# IMX291.net
KiCad netlist of a schematic drawn in Altium Designer
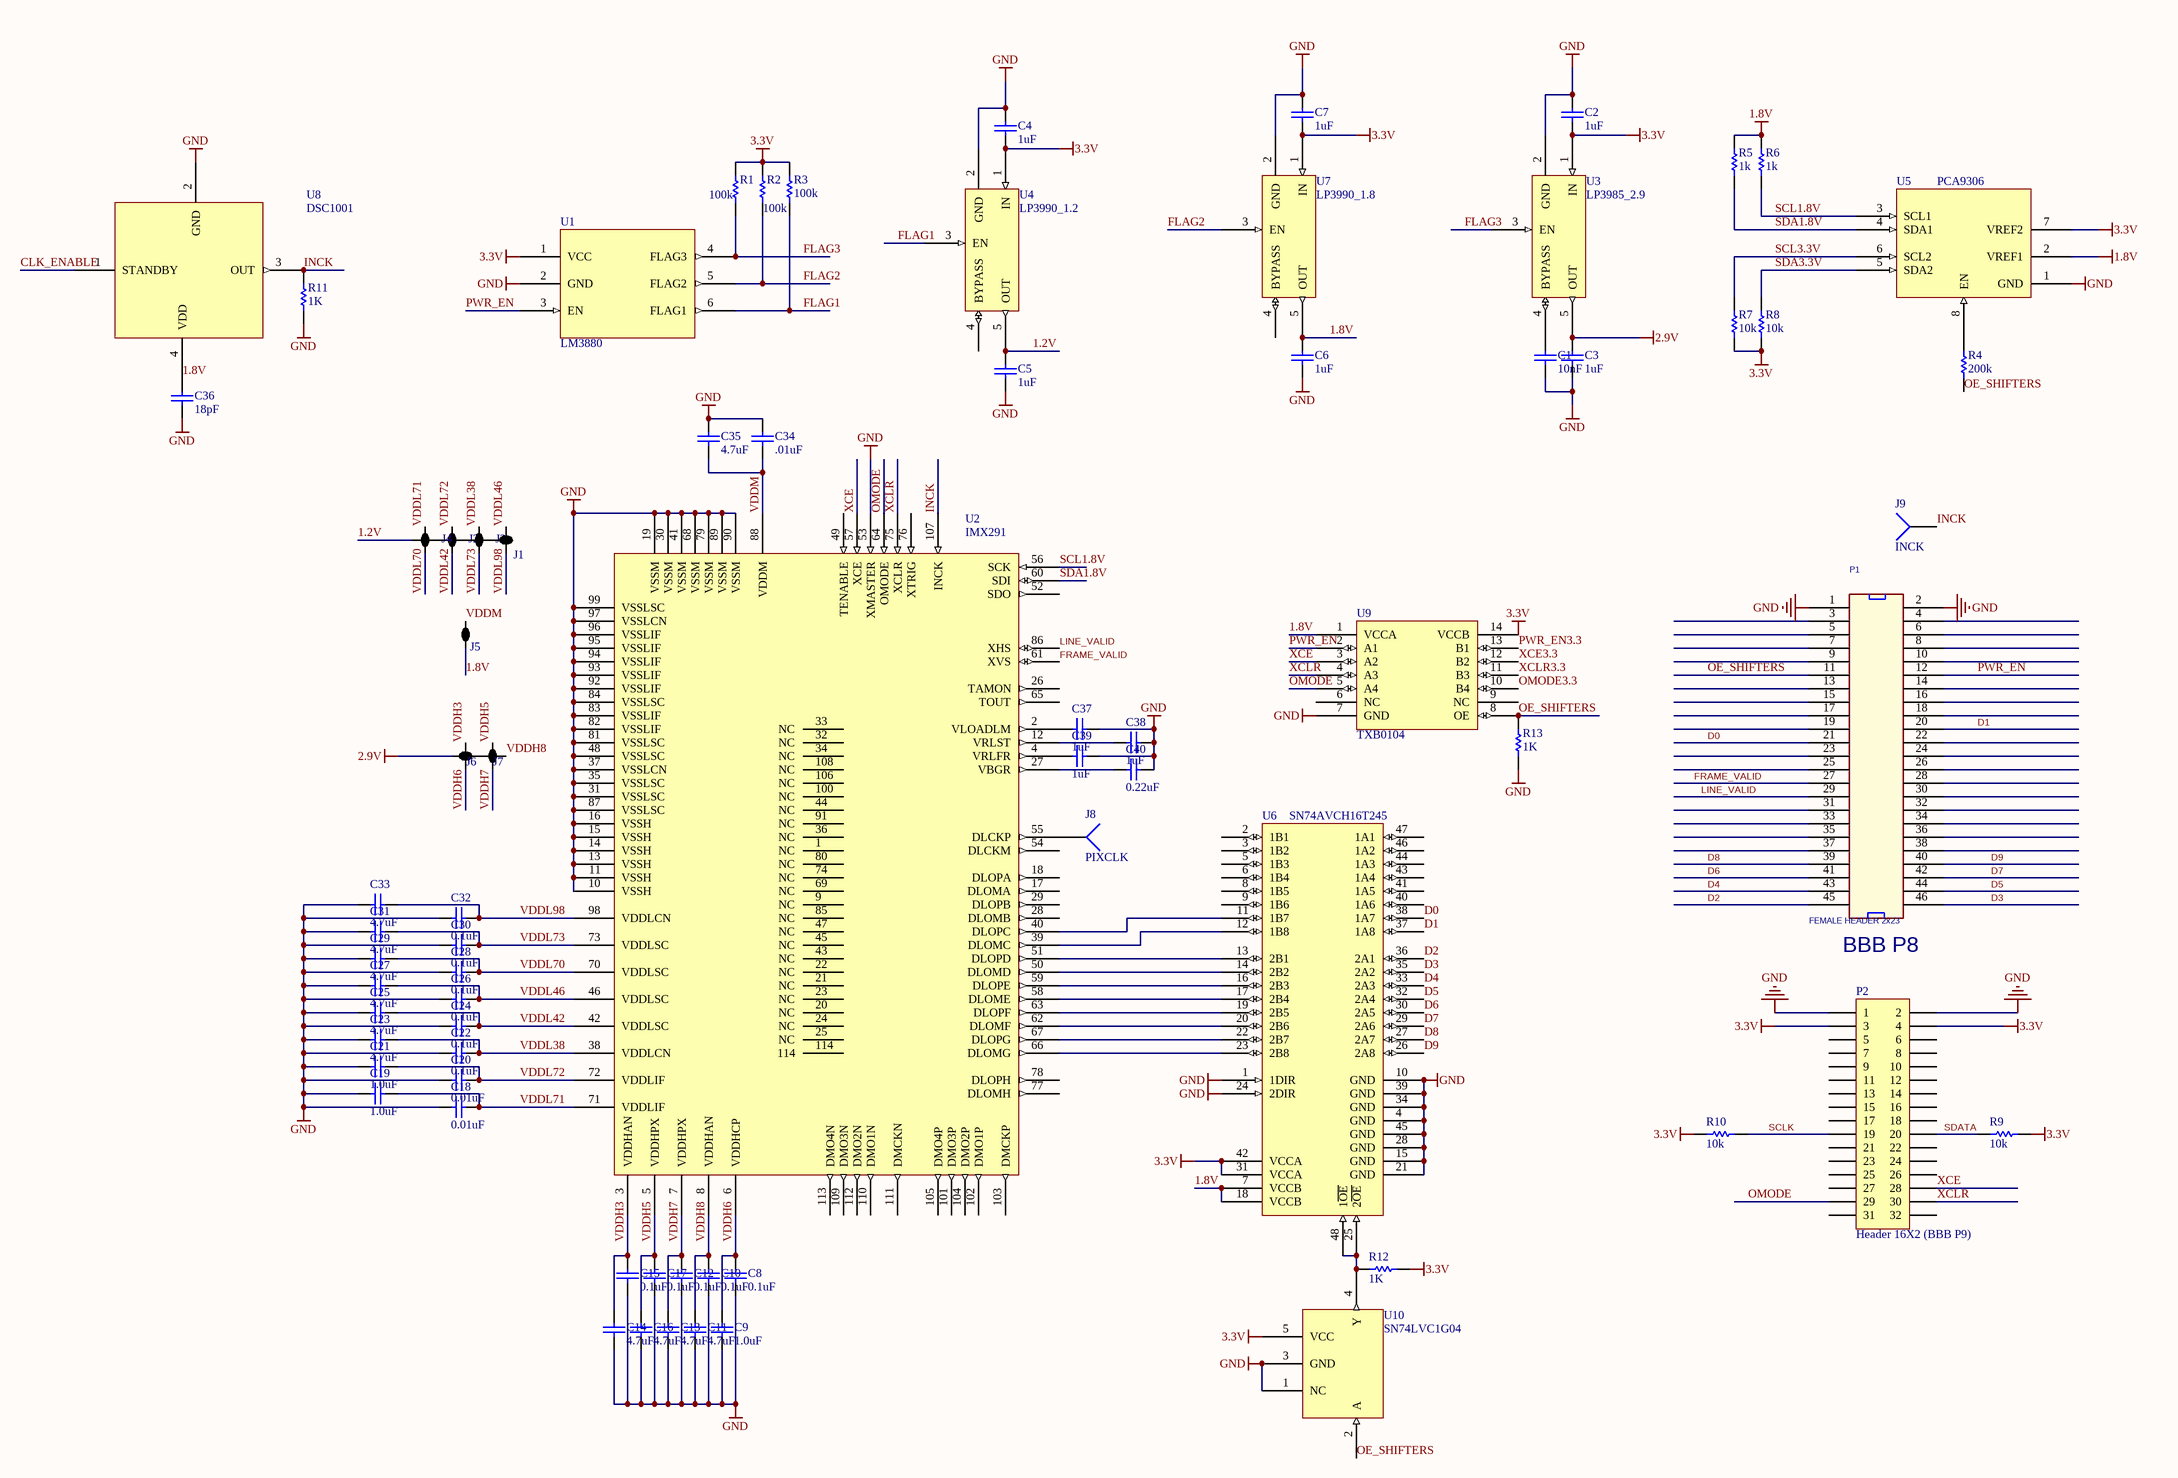
[diagram p0: IMX291.SchDoc]

(export (version "E")
  (design (tool "Eeschema 10.0.6"))
  (components
    (comp (ref "C1") (value "10nF") (footprint "0603") (libsource (lib "IMX291") (part "cap")))
    (comp (ref "C2") (value "1uF") (footprint "0603") (libsource (lib "IMX291") (part "cap")))
    (comp (ref "C3") (value "1uF") (footprint "0603") (libsource (lib "IMX291") (part "cap")))
    (comp (ref "C4") (value "1uF") (footprint "0603") (libsource (lib "IMX291") (part "cap")))
    (comp (ref "C5") (value "1uF") (footprint "0603") (libsource (lib "IMX291") (part "cap")))
    (comp (ref "C6") (value "1uF") (footprint "0603") (libsource (lib "IMX291") (part "cap")))
    (comp (ref "C7") (value "1uF") (footprint "0603") (libsource (lib "IMX291") (part "cap")))
    (comp (ref "C8") (value "0.1uF") (footprint "0603") (libsource (lib "IMX291") (part "cap")))
    (comp (ref "C9") (value "1.0uF") (footprint "0603") (libsource (lib "IMX291") (part "cap")))
    (comp (ref "C10") (value "0.1uF") (footprint "0603") (libsource (lib "IMX291") (part "cap")))
    (comp (ref "C11") (value "4.7uF") (footprint "0603") (libsource (lib "IMX291") (part "cap")))
    (comp (ref "C12") (value "0.1uF") (footprint "0603") (libsource (lib "IMX291") (part "cap")))
    (comp (ref "C13") (value "4.7uF") (footprint "0603") (libsource (lib "IMX291") (part "cap")))
    (comp (ref "C14") (value "4.7uF") (footprint "0603") (libsource (lib "IMX291") (part "cap")))
    (comp (ref "C15") (value "0.1uF") (footprint "0603") (libsource (lib "IMX291") (part "cap")))
    (comp (ref "C16") (value "4.7uF") (footprint "0603") (libsource (lib "IMX291") (part "cap")))
    (comp (ref "C17") (value "0.1uF") (footprint "0603") (libsource (lib "IMX291") (part "cap")))
    (comp (ref "C18") (value "0.01uF") (footprint "0603") (libsource (lib "IMX291") (part "cap")))
    (comp (ref "C19") (value "1.0uF") (footprint "0603") (libsource (lib "IMX291") (part "cap")))
    (comp (ref "C20") (value "0.01uF") (footprint "0603") (libsource (lib "IMX291") (part "cap")))
    (comp (ref "C21") (value "1.0uF") (footprint "0603") (libsource (lib "IMX291") (part "cap")))
    (comp (ref "C22") (value "0.1uF") (footprint "0603") (libsource (lib "IMX291") (part "cap")))
    (comp (ref "C23") (value "4.7uF") (footprint "0603") (libsource (lib "IMX291") (part "cap")))
    (comp (ref "C24") (value "0.1uF") (footprint "0603") (libsource (lib "IMX291") (part "cap")))
    (comp (ref "C25") (value "4.7uF") (footprint "0603") (libsource (lib "IMX291") (part "cap")))
    (comp (ref "C26") (value "0.1uF") (footprint "0603") (libsource (lib "IMX291") (part "cap")))
    (comp (ref "C27") (value "4.7uF") (footprint "0603") (libsource (lib "IMX291") (part "cap")))
    (comp (ref "C28") (value "0.1uF") (footprint "0603") (libsource (lib "IMX291") (part "cap")))
    (comp (ref "C29") (value "4.7uF") (footprint "0603") (libsource (lib "IMX291") (part "cap")))
    (comp (ref "C30") (value "0.1uF") (footprint "0603") (libsource (lib "IMX291") (part "cap")))
    (comp (ref "C31") (value "4.7uF") (footprint "0603") (libsource (lib "IMX291") (part "cap")))
    (comp (ref "C32") (value "0.1uF") (footprint "0603") (libsource (lib "IMX291") (part "cap")))
    (comp (ref "C33") (value "4.7uF") (footprint "0603") (libsource (lib "IMX291") (part "cap")))
    (comp (ref "C34") (value ".01uF") (footprint "0603") (libsource (lib "IMX291") (part "cap")))
    (comp (ref "C35") (value "4.7uF") (footprint "0603") (libsource (lib "IMX291") (part "cap")))
    (comp (ref "C36") (value "18pF") (footprint "0603") (libsource (lib "IMX291") (part "cap")))
    (comp (ref "C37") (value "1uF") (footprint "0603") (libsource (lib "IMX291") (part "cap")))
    (comp (ref "C38") (value "1uF") (footprint "0603") (libsource (lib "IMX291") (part "cap")))
    (comp (ref "C39") (value "1uF") (footprint "0603") (libsource (lib "IMX291") (part "cap")))
    (comp (ref "C40") (value "0.22uF") (footprint "0603") (libsource (lib "IMX291") (part "cap")))
    (comp (ref "J1")
      (value "3 way net tie junction T shape")
      (footprint "3wayT_LP")
      (libsource (lib "NetTieLib") (part "3wayT"))
    )
    (comp (ref "J2")
      (value "4 way net tie junction")
      (footprint "4way_LP")
      (libsource (lib "") (part "4way_1"))
    )
    (comp (ref "J3")
      (value "4 way net tie junction")
      (footprint "4way_LP")
      (libsource (lib "") (part "4way_1"))
    )
    (comp (ref "J4")
      (value "4 way net tie junction")
      (footprint "4way_LP")
      (libsource (lib "") (part "4way_1"))
    )
    (comp (ref "J5")
      (value "2 way net tie junction")
      (footprint "2way_LP")
      (libsource (lib "NetTieLib") (part "2way"))
    )
    (comp (ref "J6")
      (value "4 way net tie junction")
      (footprint "4way_LP")
      (libsource (lib "NetTieLib") (part "4way"))
    )
    (comp (ref "J7")
      (value "4 way net tie junction")
      (footprint "4way_LP")
      (libsource (lib "") (part "4way_1"))
    )
    (comp (ref "J8")
      (value "PIXCLK")
      (footprint "PIN1")
      (description "Socket")
      (fields (field (name "PUBLISHER") "Altium Limited"))
      (libsource (lib "Miscellaneous Connectors") (part "Socket"))
    )
    (comp (ref "J9")
      (value "INCK")
      (footprint "PIN1")
      (description "Socket")
      (fields (field (name "PUBLISHER") "Altium Limited"))
      (libsource (lib "Miscellaneous Connectors") (part "Socket"))
    )
    (comp (ref "P1")
      (value "FEMALE HEADER 2x23")
      (description "CONN HEADER FMAL 46PS.1\" DL GOLD")
      (fields
        (field (name "MANUFACTURER") "Sullins Connector Solutions")
        (field (name "MANUFACTURER PART NUMBER") "PPPC232LFBN-RC")
      )
      (libsource (lib "IMX291") (part "HDR_46_F_2_0.1_0.1"))
    )
    (comp (ref "P2")
      (value "Header 16X2 (BBB P9)")
      (footprint "HDR2X16")
      (description "Header, 16-Pin, Dual row")
      (fields (field (name "PUBLISHER") "Altium Limited"))
      (libsource (lib "Miscellaneous Connectors") (part "Header 16X2"))
    )
    (comp (ref "R1")
      (value "100k")
      (footprint "0603")
      (description "resistor")
      (libsource (lib "IMX291") (part "res"))
    )
    (comp (ref "R2")
      (value "100k")
      (footprint "0603")
      (description "resistor")
      (libsource (lib "IMX291") (part "res"))
    )
    (comp (ref "R3")
      (value "100k")
      (footprint "0603")
      (description "resistor")
      (libsource (lib "IMX291") (part "res"))
    )
    (comp (ref "R4")
      (value "200k")
      (footprint "0603")
      (description "resistor")
      (libsource (lib "IMX291") (part "res"))
    )
    (comp (ref "R5")
      (value "1k")
      (footprint "0603")
      (description "resistor")
      (libsource (lib "IMX291") (part "res"))
    )
    (comp (ref "R6")
      (value "1k")
      (footprint "0603")
      (description "resistor")
      (libsource (lib "IMX291") (part "res"))
    )
    (comp (ref "R7")
      (value "10k")
      (footprint "0603")
      (description "resistor")
      (libsource (lib "IMX291") (part "res"))
    )
    (comp (ref "R8")
      (value "10k")
      (footprint "0603")
      (description "resistor")
      (libsource (lib "IMX291") (part "res"))
    )
    (comp (ref "R9")
      (value "10k")
      (footprint "0603")
      (description "resistor")
      (libsource (lib "IMX291") (part "res"))
    )
    (comp (ref "R10")
      (value "10k")
      (footprint "0603")
      (description "resistor")
      (libsource (lib "IMX291") (part "res"))
    )
    (comp (ref "R11") (value "1K") (footprint "0603") (libsource (lib "") (part "res_1")))
    (comp (ref "R12") (value "1K") (footprint "0603") (libsource (lib "") (part "res_1")))
    (comp (ref "R13") (value "1K") (footprint "0603") (libsource (lib "") (part "res_1")))
    (comp (ref "U1") (value "LM3880") (footprint "SOT23-6_M") (libsource (lib "IMX291") (part "LM3880")))
    (comp (ref "U2")
      (value "IMX291")
      (footprint "LGA110C80P14X11_1200X930X350")
      (libsource (lib "IMX291") (part "IMX291"))
    )
    (comp (ref "U3") (value "LP3985_2.9") (footprint "DBV005") (libsource (lib "IMX291") (part "LP3985")))
    (comp (ref "U4") (value "LP3990_1.2") (footprint "DBV005") (libsource (lib "IMX291") (part "LP3990")))
    (comp (ref "U5") (value "PCA9306") (footprint "D008_M") (libsource (lib "IMX291") (part "PCA9306")))
    (comp (ref "U6")
      (value "SN74AVCH16T245")
      (footprint "TSSOP48")
      (libsource (lib "IMX291") (part "SN74AVCH16T245"))
    )
    (comp (ref "U7") (value "LP3990_1.8") (footprint "DBV005") (libsource (lib "IMX291") (part "LP3990")))
    (comp (ref "U8") (value "DSC1001") (footprint "DSC1001") (libsource (lib "IMX291") (part "DSC1001")))
    (comp (ref "U9") (value "TXB0104") (footprint "TSSOP14_M") (libsource (lib "IMX291") (part "TXB0104")))
    (comp (ref "U10")
      (value "SN74LVC1G04")
      (footprint "DBV005")
      (libsource (lib "IMX291") (part "SN74LVC1G04"))
    )
  )
  (nets
    (net (code "1") (name "/1.2V") (class "Default")
      (node (ref "C5") (pin "2") (pinfunction "2_2") (pintype "passive"))
      (node (ref "J4") (pin "3") (pinfunction "3_3") (pintype "passive"))
      (node (ref "U4") (pin "5") (pinfunction "OUT_5") (pintype "output"))
    )
    (net (code "2") (name "/CLK_ENABLE") (class "Default")
      (node (ref "U8") (pin "1") (pinfunction "STANDBY_1") (pintype "passive"))
    )
    (net (code "3") (name "/D0") (class "Default")
      (node (ref "P1") (pin "21") (pinfunction "11_21") (pintype "passive"))
      (node (ref "U6") (pin "38") (pinfunction "1A7_38") (pintype "bidirectional"))
    )
    (net (code "4") (name "/D1") (class "Default")
      (node (ref "P1") (pin "20") (pinfunction "35_20") (pintype "passive"))
      (node (ref "U6") (pin "37") (pinfunction "1A8_37") (pintype "bidirectional"))
    )
    (net (code "5") (name "/D2") (class "Default")
      (node (ref "P1") (pin "45") (pinfunction "23_45") (pintype "passive"))
      (node (ref "U6") (pin "36") (pinfunction "2A1_36") (pintype "bidirectional"))
    )
    (net (code "6") (name "/D3") (class "Default")
      (node (ref "P1") (pin "46") (pinfunction "48_46") (pintype "passive"))
      (node (ref "U6") (pin "35") (pinfunction "2A2_35") (pintype "bidirectional"))
    )
    (net (code "7") (name "/D4") (class "Default")
      (node (ref "P1") (pin "43") (pinfunction "22_43") (pintype "passive"))
      (node (ref "U6") (pin "33") (pinfunction "2A3_33") (pintype "bidirectional"))
    )
    (net (code "8") (name "/D5") (class "Default")
      (node (ref "P1") (pin "44") (pinfunction "47_44") (pintype "passive"))
      (node (ref "U6") (pin "32") (pinfunction "2A4_32") (pintype "bidirectional"))
    )
    (net (code "9") (name "/D6") (class "Default")
      (node (ref "P1") (pin "41") (pinfunction "21_41") (pintype "passive"))
      (node (ref "U6") (pin "30") (pinfunction "2A5_30") (pintype "bidirectional"))
    )
    (net (code "10") (name "/D7") (class "Default")
      (node (ref "P1") (pin "42") (pinfunction "46_42") (pintype "passive"))
      (node (ref "U6") (pin "29") (pinfunction "2A6_29") (pintype "bidirectional"))
    )
    (net (code "11") (name "/D8") (class "Default")
      (node (ref "P1") (pin "39") (pinfunction "20_39") (pintype "passive"))
      (node (ref "U6") (pin "27") (pinfunction "2A7_27") (pintype "bidirectional"))
    )
    (net (code "12") (name "/D9") (class "Default")
      (node (ref "P1") (pin "40") (pinfunction "45_40") (pintype "passive"))
      (node (ref "U6") (pin "26") (pinfunction "2A8_26") (pintype "bidirectional"))
    )
    (net (code "13") (name "/FLAG1") (class "Default")
      (node (ref "R3") (pin "1") (pinfunction "1_1") (pintype "passive"))
      (node (ref "U1") (pin "6") (pinfunction "FLAG1_6") (pintype "output"))
      (node (ref "U4") (pin "3") (pinfunction "EN_3") (pintype "input"))
    )
    (net (code "14") (name "/FLAG2") (class "Default")
      (node (ref "R2") (pin "1") (pinfunction "1_1") (pintype "passive"))
      (node (ref "U1") (pin "5") (pinfunction "FLAG2_5") (pintype "output"))
      (node (ref "U7") (pin "3") (pinfunction "EN_3") (pintype "input"))
    )
    (net (code "15") (name "/FLAG3") (class "Default")
      (node (ref "R1") (pin "1") (pinfunction "1_1") (pintype "passive"))
      (node (ref "U1") (pin "4") (pinfunction "FLAG3_4") (pintype "output"))
      (node (ref "U3") (pin "3") (pinfunction "EN_3") (pintype "input"))
    )
    (net (code "16") (name "/FRAME_VALID") (class "Default")
      (node (ref "P1") (pin "27") (pinfunction "14_27") (pintype "passive"))
      (node (ref "U2") (pin "61") (pinfunction "XVS_61") (pintype "bidirectional"))
    )
    (net (code "17") (name "/INCK") (class "Default")
      (node (ref "J9") (pin "1") (pinfunction "1_1") (pintype "passive"))
      (node (ref "R11") (pin "2") (pinfunction "2_2") (pintype "passive"))
      (node (ref "U2") (pin "107") (pinfunction "INCK_107") (pintype "input"))
      (node (ref "U8") (pin "3") (pinfunction "OUT_3") (pintype "output"))
    )
    (net (code "18") (name "/LINE_VALID") (class "Default")
      (node (ref "P1") (pin "29") (pinfunction "15_29") (pintype "passive"))
      (node (ref "U2") (pin "86") (pinfunction "XHS_86") (pintype "bidirectional"))
    )
    (net (code "19") (name "/OE_SHIFTERS") (class "Default")
      (node (ref "P1") (pin "11") (pinfunction "6_11") (pintype "passive"))
      (node (ref "R13") (pin "2") (pinfunction "2_2") (pintype "passive"))
      (node (ref "R4") (pin "1") (pinfunction "1_1") (pintype "passive"))
      (node (ref "U10") (pin "2") (pinfunction "A_2") (pintype "input"))
      (node (ref "U9") (pin "8") (pinfunction "OE_8") (pintype "bidirectional"))
    )
    (net (code "20") (name "/OMODE") (class "Default")
      (node (ref "P2") (pin "29") (pinfunction "29_29") (pintype "passive"))
      (node (ref "U2") (pin "64") (pinfunction "OMODE_64") (pintype "input"))
      (node (ref "U9") (pin "5") (pinfunction "A4_5") (pintype "bidirectional"))
    )
    (net (code "21") (name "/OMODE3.3") (class "Default")
      (node (ref "U9") (pin "10") (pinfunction "B4_10") (pintype "bidirectional"))
    )
    (net (code "22") (name "/PWR_EN") (class "Default")
      (node (ref "P1") (pin "12") (pinfunction "31_12") (pintype "passive"))
      (node (ref "U1") (pin "3") (pinfunction "EN_3") (pintype "input"))
      (node (ref "U9") (pin "2") (pinfunction "A1_2") (pintype "bidirectional"))
    )
    (net (code "23") (name "/PWR_EN3.3") (class "Default")
      (node (ref "U9") (pin "13") (pinfunction "B1_13") (pintype "bidirectional"))
    )
    (net (code "24") (name "/SCL1.8V") (class "Default")
      (node (ref "R6") (pin "1") (pinfunction "1_1") (pintype "passive"))
      (node (ref "U2") (pin "56") (pinfunction "SCK_56") (pintype "input"))
      (node (ref "U5") (pin "3") (pinfunction "SCL1_3") (pintype "input"))
    )
    (net (code "25") (name "/SCL3.3V") (class "Default")
      (node (ref "R7") (pin "2") (pinfunction "2_2") (pintype "passive"))
      (node (ref "U5") (pin "6") (pinfunction "SCL2_6") (pintype "input"))
    )
    (net (code "26") (name "/SCLK") (class "Default")
      (node (ref "P2") (pin "19") (pinfunction "19_19") (pintype "passive"))
      (node (ref "R10") (pin "2") (pinfunction "2_2") (pintype "passive"))
    )
    (net (code "27") (name "/SDA1.8V") (class "Default")
      (node (ref "R5") (pin "1") (pinfunction "1_1") (pintype "passive"))
      (node (ref "U2") (pin "60") (pinfunction "SDI_60") (pintype "bidirectional"))
      (node (ref "U5") (pin "4") (pinfunction "SDA1_4") (pintype "input"))
    )
    (net (code "28") (name "/SDA3.3V") (class "Default")
      (node (ref "R8") (pin "2") (pinfunction "2_2") (pintype "passive"))
      (node (ref "U5") (pin "5") (pinfunction "SDA2_5") (pintype "input"))
    )
    (net (code "29") (name "/SDATA") (class "Default")
      (node (ref "P2") (pin "20") (pinfunction "20_20") (pintype "passive"))
      (node (ref "R9") (pin "1") (pinfunction "1_1") (pintype "passive"))
    )
    (net (code "30") (name "/VDDH3") (class "Default")
      (node (ref "C14") (pin "2") (pinfunction "2_2") (pintype "passive"))
      (node (ref "C15") (pin "2") (pinfunction "2_2") (pintype "passive"))
      (node (ref "J6") (pin "2") (pinfunction "2_2") (pintype "passive"))
      (node (ref "U2") (pin "3") (pinfunction "VDDHAN_3") (pintype "power_in"))
    )
    (net (code "31") (name "/VDDH5") (class "Default")
      (node (ref "C16") (pin "2") (pinfunction "2_2") (pintype "passive"))
      (node (ref "C17") (pin "2") (pinfunction "2_2") (pintype "passive"))
      (node (ref "J7") (pin "1") (pinfunction "1_1") (pintype "passive"))
      (node (ref "U2") (pin "5") (pinfunction "VDDHPX_5") (pintype "power_in"))
    )
    (net (code "32") (name "/VDDH6") (class "Default")
      (node (ref "C8") (pin "1") (pinfunction "1_1") (pintype "passive"))
      (node (ref "C9") (pin "1") (pinfunction "1_1") (pintype "passive"))
      (node (ref "J6") (pin "3") (pinfunction "3_3") (pintype "passive"))
      (node (ref "U2") (pin "6") (pinfunction "VDDHCP_6") (pintype "power_in"))
    )
    (net (code "33") (name "/VDDH7") (class "Default")
      (node (ref "C12") (pin "2") (pinfunction "2_2") (pintype "passive"))
      (node (ref "C13") (pin "2") (pinfunction "2_2") (pintype "passive"))
      (node (ref "J7") (pin "4") (pinfunction "4_4") (pintype "passive"))
      (node (ref "U2") (pin "7") (pinfunction "VDDHPX_7") (pintype "power_in"))
    )
    (net (code "34") (name "/VDDH8") (class "Default")
      (node (ref "C10") (pin "2") (pinfunction "2_2") (pintype "passive"))
      (node (ref "C11") (pin "2") (pinfunction "2_2") (pintype "passive"))
      (node (ref "J7") (pin "2") (pinfunction "2_2") (pintype "passive"))
      (node (ref "U2") (pin "8") (pinfunction "VDDHAN_8") (pintype "power_in"))
    )
    (net (code "35") (name "/VDDL38") (class "Default")
      (node (ref "C22") (pin "2") (pinfunction "2_2") (pintype "passive"))
      (node (ref "C23") (pin "2") (pinfunction "2_2") (pintype "passive"))
      (node (ref "J3") (pin "1") (pinfunction "1_1") (pintype "passive"))
      (node (ref "U2") (pin "38") (pinfunction "VDDLCN_38") (pintype "power_in"))
    )
    (net (code "36") (name "/VDDL42") (class "Default")
      (node (ref "C24") (pin "2") (pinfunction "2_2") (pintype "passive"))
      (node (ref "C25") (pin "2") (pinfunction "2_2") (pintype "passive"))
      (node (ref "J2") (pin "4") (pinfunction "4_4") (pintype "passive"))
      (node (ref "U2") (pin "42") (pinfunction "VDDLSC_42") (pintype "power_in"))
    )
    (net (code "37") (name "/VDDL46") (class "Default")
      (node (ref "C26") (pin "2") (pinfunction "2_2") (pintype "passive"))
      (node (ref "C27") (pin "2") (pinfunction "2_2") (pintype "passive"))
      (node (ref "J1") (pin "2") (pinfunction "2_2") (pintype "passive"))
      (node (ref "U2") (pin "46") (pinfunction "VDDLSC_46") (pintype "power_in"))
    )
    (net (code "38") (name "/VDDL70") (class "Default")
      (node (ref "C28") (pin "2") (pinfunction "2_2") (pintype "passive"))
      (node (ref "C29") (pin "2") (pinfunction "2_2") (pintype "passive"))
      (node (ref "J4") (pin "4") (pinfunction "4_4") (pintype "passive"))
      (node (ref "U2") (pin "70") (pinfunction "VDDLSC_70") (pintype "power_in"))
    )
    (net (code "39") (name "/VDDL71") (class "Default")
      (node (ref "C18") (pin "2") (pinfunction "2_2") (pintype "passive"))
      (node (ref "C19") (pin "2") (pinfunction "2_2") (pintype "passive"))
      (node (ref "J4") (pin "1") (pinfunction "1_1") (pintype "passive"))
      (node (ref "U2") (pin "71") (pinfunction "VDDLIF_71") (pintype "power_in"))
    )
    (net (code "40") (name "/VDDL72") (class "Default")
      (node (ref "C20") (pin "2") (pinfunction "2_2") (pintype "passive"))
      (node (ref "C21") (pin "2") (pinfunction "2_2") (pintype "passive"))
      (node (ref "J2") (pin "1") (pinfunction "1_1") (pintype "passive"))
      (node (ref "U2") (pin "72") (pinfunction "VDDLIF_72") (pintype "power_in"))
    )
    (net (code "41") (name "/VDDL73") (class "Default")
      (node (ref "C30") (pin "2") (pinfunction "2_2") (pintype "passive"))
      (node (ref "C31") (pin "2") (pinfunction "2_2") (pintype "passive"))
      (node (ref "J3") (pin "4") (pinfunction "4_4") (pintype "passive"))
      (node (ref "U2") (pin "73") (pinfunction "VDDLSC_73") (pintype "power_in"))
    )
    (net (code "42") (name "/VDDL98") (class "Default")
      (node (ref "C32") (pin "2") (pinfunction "2_2") (pintype "passive"))
      (node (ref "C33") (pin "2") (pinfunction "2_2") (pintype "passive"))
      (node (ref "J1") (pin "3") (pinfunction "3_3") (pintype "passive"))
      (node (ref "U2") (pin "98") (pinfunction "VDDLCN_98") (pintype "power_in"))
    )
    (net (code "43") (name "/VDDM") (class "Default")
      (node (ref "C34") (pin "1") (pinfunction "1_1") (pintype "passive"))
      (node (ref "C35") (pin "1") (pinfunction "1_1") (pintype "passive"))
      (node (ref "J5") (pin "2") (pinfunction "2_2") (pintype "passive"))
      (node (ref "U2") (pin "88") (pinfunction "VDDM_88") (pintype "power_in"))
    )
    (net (code "44") (name "/XCE") (class "Default")
      (node (ref "P2") (pin "28") (pinfunction "28_28") (pintype "passive"))
      (node (ref "U2") (pin "57") (pinfunction "XCE_57") (pintype "input"))
      (node (ref "U9") (pin "3") (pinfunction "A2_3") (pintype "bidirectional"))
    )
    (net (code "45") (name "/XCE3.3") (class "Default")
      (node (ref "U9") (pin "12") (pinfunction "B2_12") (pintype "bidirectional"))
    )
    (net (code "46") (name "/XCLR") (class "Default")
      (node (ref "P2") (pin "30") (pinfunction "30_30") (pintype "passive"))
      (node (ref "U2") (pin "75") (pinfunction "XCLR_75") (pintype "input"))
      (node (ref "U9") (pin "4") (pinfunction "A3_4") (pintype "bidirectional"))
    )
    (net (code "47") (name "/XCLR3.3") (class "Default")
      (node (ref "U9") (pin "11") (pinfunction "B3_11") (pintype "bidirectional"))
    )
    (net (code "48") (name "1.8V") (class "Default")
      (node (ref "C36") (pin "2") (pinfunction "2_2") (pintype "passive"))
      (node (ref "C6") (pin "2") (pinfunction "2_2") (pintype "passive"))
      (node (ref "J5") (pin "1") (pinfunction "1_1") (pintype "passive"))
      (node (ref "R5") (pin "2") (pinfunction "2_2") (pintype "passive"))
      (node (ref "R6") (pin "2") (pinfunction "2_2") (pintype "passive"))
      (node (ref "U5") (pin "2") (pinfunction "VREF1_2") (pintype "power_in"))
      (node (ref "U6") (pin "18") (pinfunction "VCCB_18") (pintype "power_in"))
      (node (ref "U6") (pin "7") (pinfunction "VCCB_7") (pintype "power_in"))
      (node (ref "U7") (pin "5") (pinfunction "OUT_5") (pintype "output"))
      (node (ref "U8") (pin "4") (pinfunction "VDD_4") (pintype "passive"))
      (node (ref "U9") (pin "1") (pinfunction "VCCA_1") (pintype "power_in"))
    )
    (net (code "49") (name "2.9V") (class "Default")
      (node (ref "C3") (pin "2") (pinfunction "2_2") (pintype "passive"))
      (node (ref "J6") (pin "1") (pinfunction "1_1") (pintype "passive"))
      (node (ref "U3") (pin "5") (pinfunction "OUT_5") (pintype "output"))
    )
    (net (code "50") (name "3.3V") (class "Default")
      (node (ref "C2") (pin "1") (pinfunction "1_1") (pintype "passive"))
      (node (ref "C4") (pin "1") (pinfunction "1_1") (pintype "passive"))
      (node (ref "C7") (pin "1") (pinfunction "1_1") (pintype "passive"))
      (node (ref "P2") (pin "3") (pinfunction "3_3") (pintype "passive"))
      (node (ref "P2") (pin "4") (pinfunction "4_4") (pintype "passive"))
      (node (ref "R1") (pin "2") (pinfunction "2_2") (pintype "passive"))
      (node (ref "R10") (pin "1") (pinfunction "1_1") (pintype "passive"))
      (node (ref "R12") (pin "2") (pinfunction "2_2") (pintype "passive"))
      (node (ref "R2") (pin "2") (pinfunction "2_2") (pintype "passive"))
      (node (ref "R3") (pin "2") (pinfunction "2_2") (pintype "passive"))
      (node (ref "R7") (pin "1") (pinfunction "1_1") (pintype "passive"))
      (node (ref "R8") (pin "1") (pinfunction "1_1") (pintype "passive"))
      (node (ref "R9") (pin "2") (pinfunction "2_2") (pintype "passive"))
      (node (ref "U1") (pin "1") (pinfunction "VCC_1") (pintype "power_in"))
      (node (ref "U10") (pin "5") (pinfunction "VCC_5") (pintype "power_in"))
      (node (ref "U3") (pin "1") (pinfunction "IN_1") (pintype "input"))
      (node (ref "U4") (pin "1") (pinfunction "IN_1") (pintype "input"))
      (node (ref "U5") (pin "7") (pinfunction "VREF2_7") (pintype "power_in"))
      (node (ref "U6") (pin "31") (pinfunction "VCCA_31") (pintype "power_in"))
      (node (ref "U6") (pin "42") (pinfunction "VCCA_42") (pintype "power_in"))
      (node (ref "U7") (pin "1") (pinfunction "IN_1") (pintype "input"))
      (node (ref "U9") (pin "14") (pinfunction "VCCB_14") (pintype "power_in"))
    )
    (net (code "51") (name "GND") (class "Default")
      (node (ref "C1") (pin "1") (pinfunction "1_1") (pintype "passive"))
      (node (ref "C10") (pin "1") (pinfunction "1_1") (pintype "passive"))
      (node (ref "C11") (pin "1") (pinfunction "1_1") (pintype "passive"))
      (node (ref "C12") (pin "1") (pinfunction "1_1") (pintype "passive"))
      (node (ref "C13") (pin "1") (pinfunction "1_1") (pintype "passive"))
      (node (ref "C14") (pin "1") (pinfunction "1_1") (pintype "passive"))
      (node (ref "C15") (pin "1") (pinfunction "1_1") (pintype "passive"))
      (node (ref "C16") (pin "1") (pinfunction "1_1") (pintype "passive"))
      (node (ref "C17") (pin "1") (pinfunction "1_1") (pintype "passive"))
      (node (ref "C18") (pin "1") (pinfunction "1_1") (pintype "passive"))
      (node (ref "C19") (pin "1") (pinfunction "1_1") (pintype "passive"))
      (node (ref "C2") (pin "2") (pinfunction "2_2") (pintype "passive"))
      (node (ref "C20") (pin "1") (pinfunction "1_1") (pintype "passive"))
      (node (ref "C21") (pin "1") (pinfunction "1_1") (pintype "passive"))
      (node (ref "C22") (pin "1") (pinfunction "1_1") (pintype "passive"))
      (node (ref "C23") (pin "1") (pinfunction "1_1") (pintype "passive"))
      (node (ref "C24") (pin "1") (pinfunction "1_1") (pintype "passive"))
      (node (ref "C25") (pin "1") (pinfunction "1_1") (pintype "passive"))
      (node (ref "C26") (pin "1") (pinfunction "1_1") (pintype "passive"))
      (node (ref "C27") (pin "1") (pinfunction "1_1") (pintype "passive"))
      (node (ref "C28") (pin "1") (pinfunction "1_1") (pintype "passive"))
      (node (ref "C29") (pin "1") (pinfunction "1_1") (pintype "passive"))
      (node (ref "C3") (pin "1") (pinfunction "1_1") (pintype "passive"))
      (node (ref "C30") (pin "1") (pinfunction "1_1") (pintype "passive"))
      (node (ref "C31") (pin "1") (pinfunction "1_1") (pintype "passive"))
      (node (ref "C32") (pin "1") (pinfunction "1_1") (pintype "passive"))
      (node (ref "C33") (pin "1") (pinfunction "1_1") (pintype "passive"))
      (node (ref "C34") (pin "2") (pinfunction "2_2") (pintype "passive"))
      (node (ref "C35") (pin "2") (pinfunction "2_2") (pintype "passive"))
      (node (ref "C36") (pin "1") (pinfunction "1_1") (pintype "passive"))
      (node (ref "C37") (pin "2") (pinfunction "2_2") (pintype "passive"))
      (node (ref "C38") (pin "2") (pinfunction "2_2") (pintype "passive"))
      (node (ref "C39") (pin "2") (pinfunction "2_2") (pintype "passive"))
      (node (ref "C4") (pin "2") (pinfunction "2_2") (pintype "passive"))
      (node (ref "C40") (pin "2") (pinfunction "2_2") (pintype "passive"))
      (node (ref "C5") (pin "1") (pinfunction "1_1") (pintype "passive"))
      (node (ref "C6") (pin "1") (pinfunction "1_1") (pintype "passive"))
      (node (ref "C7") (pin "2") (pinfunction "2_2") (pintype "passive"))
      (node (ref "C8") (pin "2") (pinfunction "2_2") (pintype "passive"))
      (node (ref "C9") (pin "2") (pinfunction "2_2") (pintype "passive"))
      (node (ref "P1") (pin "1") (pinfunction "1_1") (pintype "passive"))
      (node (ref "P1") (pin "2") (pinfunction "26_2") (pintype "passive"))
      (node (ref "P2") (pin "1") (pinfunction "1_1") (pintype "passive"))
      (node (ref "P2") (pin "2") (pinfunction "2_2") (pintype "passive"))
      (node (ref "R11") (pin "1") (pinfunction "1_1") (pintype "passive"))
      (node (ref "R13") (pin "1") (pinfunction "1_1") (pintype "passive"))
      (node (ref "U1") (pin "2") (pinfunction "GND_2") (pintype "power_in"))
      (node (ref "U10") (pin "1") (pinfunction "NC_1") (pintype "passive"))
      (node (ref "U10") (pin "3") (pinfunction "GND_3") (pintype "power_in"))
      (node (ref "U2") (pin "10") (pinfunction "VSSH_10") (pintype "power_in"))
      (node (ref "U2") (pin "11") (pinfunction "VSSH_11") (pintype "power_in"))
      (node (ref "U2") (pin "13") (pinfunction "VSSH_13") (pintype "power_in"))
      (node (ref "U2") (pin "14") (pinfunction "VSSH_14") (pintype "power_in"))
      (node (ref "U2") (pin "15") (pinfunction "VSSH_15") (pintype "power_in"))
      (node (ref "U2") (pin "16") (pinfunction "VSSH_16") (pintype "power_in"))
      (node (ref "U2") (pin "19") (pinfunction "VSSM_19") (pintype "power_in"))
      (node (ref "U2") (pin "30") (pinfunction "VSSM_30") (pintype "power_in"))
      (node (ref "U2") (pin "31") (pinfunction "VSSLSC_31") (pintype "power_in"))
      (node (ref "U2") (pin "35") (pinfunction "VSSLSC_35") (pintype "power_in"))
      (node (ref "U2") (pin "37") (pinfunction "VSSLCN_37") (pintype "power_in"))
      (node (ref "U2") (pin "41") (pinfunction "VSSM_41") (pintype "power_in"))
      (node (ref "U2") (pin "48") (pinfunction "VSSLSC_48") (pintype "power_in"))
      (node (ref "U2") (pin "53") (pinfunction "XMASTER_53") (pintype "input"))
      (node (ref "U2") (pin "68") (pinfunction "VSSM_68") (pintype "power_in"))
      (node (ref "U2") (pin "79") (pinfunction "VSSM_79") (pintype "power_in"))
      (node (ref "U2") (pin "81") (pinfunction "VSSLSC_81") (pintype "power_in"))
      (node (ref "U2") (pin "82") (pinfunction "VSSLIF_82") (pintype "power_in"))
      (node (ref "U2") (pin "83") (pinfunction "VSSLIF_83") (pintype "power_in"))
      (node (ref "U2") (pin "84") (pinfunction "VSSLSC_84") (pintype "power_in"))
      (node (ref "U2") (pin "87") (pinfunction "VSSLSC_87") (pintype "power_in"))
      (node (ref "U2") (pin "89") (pinfunction "VSSM_89") (pintype "power_in"))
      (node (ref "U2") (pin "90") (pinfunction "VSSM_90") (pintype "power_in"))
      (node (ref "U2") (pin "92") (pinfunction "VSSLIF_92") (pintype "power_in"))
      (node (ref "U2") (pin "93") (pinfunction "VSSLIF_93") (pintype "power_in"))
      (node (ref "U2") (pin "94") (pinfunction "VSSLIF_94") (pintype "power_in"))
      (node (ref "U2") (pin "95") (pinfunction "VSSLIF_95") (pintype "power_in"))
      (node (ref "U2") (pin "96") (pinfunction "VSSLIF_96") (pintype "power_in"))
      (node (ref "U2") (pin "97") (pinfunction "VSSLCN_97") (pintype "power_in"))
      (node (ref "U2") (pin "99") (pinfunction "VSSLSC_99") (pintype "power_in"))
      (node (ref "U3") (pin "2") (pinfunction "GND_2") (pintype "power_in"))
      (node (ref "U4") (pin "2") (pinfunction "GND_2") (pintype "power_in"))
      (node (ref "U5") (pin "1") (pinfunction "GND_1") (pintype "power_in"))
      (node (ref "U6") (pin "1") (pinfunction "1DIR_1") (pintype "input"))
      (node (ref "U6") (pin "10") (pinfunction "GND_10") (pintype "power_in"))
      (node (ref "U6") (pin "15") (pinfunction "GND_15") (pintype "power_in"))
      (node (ref "U6") (pin "21") (pinfunction "GND_21") (pintype "power_in"))
      (node (ref "U6") (pin "24") (pinfunction "2DIR_24") (pintype "input"))
      (node (ref "U6") (pin "28") (pinfunction "GND_28") (pintype "power_in"))
      (node (ref "U6") (pin "34") (pinfunction "GND_34") (pintype "power_in"))
      (node (ref "U6") (pin "39") (pinfunction "GND_39") (pintype "power_in"))
      (node (ref "U6") (pin "4") (pinfunction "GND_4") (pintype "power_in"))
      (node (ref "U6") (pin "45") (pinfunction "GND_45") (pintype "power_in"))
      (node (ref "U7") (pin "2") (pinfunction "GND_2") (pintype "power_in"))
      (node (ref "U8") (pin "2") (pinfunction "GND_2") (pintype "passive"))
      (node (ref "U9") (pin "7") (pinfunction "GND_7") (pintype "power_in"))
    )
    (net (code "52") (name "Net-(J1-Pad1)") (class "Default")
      (node (ref "J1") (pin "1") (pinfunction "1_1") (pintype "passive"))
      (node (ref "J3") (pin "2") (pinfunction "2_2") (pintype "passive"))
    )
    (net (code "53") (name "Net-(J2-Pad2)") (class "Default")
      (node (ref "J2") (pin "2") (pinfunction "2_2") (pintype "passive"))
      (node (ref "J3") (pin "3") (pinfunction "3_3") (pintype "passive"))
    )
    (net (code "54") (name "Net-(J2-Pad3)") (class "Default")
      (node (ref "J2") (pin "3") (pinfunction "3_3") (pintype "passive"))
      (node (ref "J4") (pin "2") (pinfunction "2_2") (pintype "passive"))
    )
    (net (code "55") (name "Net-(J6-Pad4)") (class "Default")
      (node (ref "J6") (pin "4") (pinfunction "4_4") (pintype "passive"))
      (node (ref "J7") (pin "3") (pinfunction "3_3") (pintype "passive"))
    )
    (net (code "56") (name "Net-(U2-DLCKP)") (class "Default")
      (node (ref "J8") (pin "1") (pinfunction "1_1") (pintype "passive"))
      (node (ref "U2") (pin "55") (pinfunction "DLCKP_55") (pintype "output"))
    )
    (net (code "57") (name "Net-(U2-DLOMC)") (class "Default")
      (node (ref "U2") (pin "39") (pinfunction "DLOMC_39") (pintype "output"))
      (node (ref "U6") (pin "12") (pinfunction "1B8_12") (pintype "bidirectional"))
    )
    (net (code "58") (name "Net-(U2-DLOMD)") (class "Default")
      (node (ref "U2") (pin "50") (pinfunction "DLOMD_50") (pintype "output"))
      (node (ref "U6") (pin "14") (pinfunction "2B2_14") (pintype "bidirectional"))
    )
    (net (code "59") (name "Net-(U2-DLOME)") (class "Default")
      (node (ref "U2") (pin "58") (pinfunction "DLOME_58") (pintype "output"))
      (node (ref "U6") (pin "17") (pinfunction "2B4_17") (pintype "bidirectional"))
    )
    (net (code "60") (name "Net-(U2-DLOMF)") (class "Default")
      (node (ref "U2") (pin "62") (pinfunction "DLOMF_62") (pintype "output"))
      (node (ref "U6") (pin "20") (pinfunction "2B6_20") (pintype "bidirectional"))
    )
    (net (code "61") (name "Net-(U2-DLOMG)") (class "Default")
      (node (ref "U2") (pin "66") (pinfunction "DLOMG_66") (pintype "output"))
      (node (ref "U6") (pin "23") (pinfunction "2B8_23") (pintype "bidirectional"))
    )
    (net (code "62") (name "Net-(U2-DLOPC)") (class "Default")
      (node (ref "U2") (pin "40") (pinfunction "DLOPC_40") (pintype "output"))
      (node (ref "U6") (pin "11") (pinfunction "1B7_11") (pintype "bidirectional"))
    )
    (net (code "63") (name "Net-(U2-DLOPD)") (class "Default")
      (node (ref "U2") (pin "51") (pinfunction "DLOPD_51") (pintype "output"))
      (node (ref "U6") (pin "13") (pinfunction "2B1_13") (pintype "bidirectional"))
    )
    (net (code "64") (name "Net-(U2-DLOPE)") (class "Default")
      (node (ref "U2") (pin "59") (pinfunction "DLOPE_59") (pintype "output"))
      (node (ref "U6") (pin "16") (pinfunction "2B3_16") (pintype "bidirectional"))
    )
    (net (code "65") (name "Net-(U2-DLOPF)") (class "Default")
      (node (ref "U2") (pin "63") (pinfunction "DLOPF_63") (pintype "output"))
      (node (ref "U6") (pin "19") (pinfunction "2B5_19") (pintype "bidirectional"))
    )
    (net (code "66") (name "Net-(U2-DLOPG)") (class "Default")
      (node (ref "U2") (pin "67") (pinfunction "DLOPG_67") (pintype "output"))
      (node (ref "U6") (pin "22") (pinfunction "2B7_22") (pintype "bidirectional"))
    )
    (net (code "67") (name "Net-(U2-VBGR)") (class "Default")
      (node (ref "C40") (pin "1") (pinfunction "1_1") (pintype "passive"))
      (node (ref "U2") (pin "27") (pinfunction "VBGR_27") (pintype "output"))
    )
    (net (code "68") (name "Net-(U2-VLOADLM)") (class "Default")
      (node (ref "C37") (pin "1") (pinfunction "1_1") (pintype "passive"))
      (node (ref "U2") (pin "2") (pinfunction "VLOADLM_2") (pintype "output"))
    )
    (net (code "69") (name "Net-(U2-VRLFR)") (class "Default")
      (node (ref "C39") (pin "1") (pinfunction "1_1") (pintype "passive"))
      (node (ref "U2") (pin "4") (pinfunction "VRLFR_4") (pintype "output"))
    )
    (net (code "70") (name "Net-(U2-VRLST)") (class "Default")
      (node (ref "C38") (pin "1") (pinfunction "1_1") (pintype "passive"))
      (node (ref "U2") (pin "12") (pinfunction "VRLST_12") (pintype "output"))
    )
    (net (code "71") (name "Net-(U3-BYPASS)") (class "Default")
      (node (ref "C1") (pin "2") (pinfunction "2_2") (pintype "passive"))
      (node (ref "U3") (pin "4") (pinfunction "BYPASS_4") (pintype "bidirectional"))
    )
    (net (code "72") (name "Net-(U5-EN)") (class "Default")
      (node (ref "R4") (pin "2") (pinfunction "2_2") (pintype "passive"))
      (node (ref "U5") (pin "8") (pinfunction "EN_8") (pintype "input"))
    )
    (net (code "73") (name "Net-(U10-Y)") (class "Default")
      (node (ref "R12") (pin "1") (pinfunction "1_1") (pintype "passive"))
      (node (ref "U10") (pin "4") (pinfunction "Y_4") (pintype "output"))
      (node (ref "U6") (pin "25") (pinfunction "2~{OE}_25") (pintype "input"))
      (node (ref "U6") (pin "48") (pinfunction "1~{OE}_48") (pintype "input"))
    )
    (net (code "74") (name "unconnected-(P1-2-Pad3)") (class "Default")
      (node (ref "P1") (pin "3") (pinfunction "2_3") (pintype "passive"))
    )
    (net (code "75") (name "unconnected-(P1-3-Pad5)") (class "Default")
      (node (ref "P1") (pin "5") (pinfunction "3_5") (pintype "passive"))
    )
    (net (code "76") (name "unconnected-(P1-4-Pad7)") (class "Default")
      (node (ref "P1") (pin "7") (pinfunction "4_7") (pintype "passive"))
    )
    (net (code "77") (name "unconnected-(P1-5-Pad9)") (class "Default")
      (node (ref "P1") (pin "9") (pinfunction "5_9") (pintype "passive"))
    )
    (net (code "78") (name "unconnected-(P1-7-Pad13)") (class "Default")
      (node (ref "P1") (pin "13") (pinfunction "7_13") (pintype "passive"))
    )
    (net (code "79") (name "unconnected-(P1-8-Pad15)") (class "Default")
      (node (ref "P1") (pin "15") (pinfunction "8_15") (pintype "passive"))
    )
    (net (code "80") (name "unconnected-(P1-9-Pad17)") (class "Default")
      (node (ref "P1") (pin "17") (pinfunction "9_17") (pintype "passive"))
    )
    (net (code "81") (name "unconnected-(P1-10-Pad19)") (class "Default")
      (node (ref "P1") (pin "19") (pinfunction "10_19") (pintype "passive"))
    )
    (net (code "82") (name "unconnected-(P1-12-Pad23)") (class "Default")
      (node (ref "P1") (pin "23") (pinfunction "12_23") (pintype "passive"))
    )
    (net (code "83") (name "unconnected-(P1-13-Pad25)") (class "Default")
      (node (ref "P1") (pin "25") (pinfunction "13_25") (pintype "passive"))
    )
    (net (code "84") (name "unconnected-(P1-16-Pad31)") (class "Default")
      (node (ref "P1") (pin "31") (pinfunction "16_31") (pintype "passive"))
    )
    (net (code "85") (name "unconnected-(P1-17-Pad33)") (class "Default")
      (node (ref "P1") (pin "33") (pinfunction "17_33") (pintype "passive"))
    )
    (net (code "86") (name "unconnected-(P1-18-Pad35)") (class "Default")
      (node (ref "P1") (pin "35") (pinfunction "18_35") (pintype "passive"))
    )
    (net (code "87") (name "unconnected-(P1-19-Pad37)") (class "Default")
      (node (ref "P1") (pin "37") (pinfunction "19_37") (pintype "passive"))
    )
    (net (code "88") (name "unconnected-(P1-27-Pad4)") (class "Default")
      (node (ref "P1") (pin "4") (pinfunction "27_4") (pintype "passive"))
    )
    (net (code "89") (name "unconnected-(P1-28-Pad6)") (class "Default")
      (node (ref "P1") (pin "6") (pinfunction "28_6") (pintype "passive"))
    )
    (net (code "90") (name "unconnected-(P1-29-Pad8)") (class "Default")
      (node (ref "P1") (pin "8") (pinfunction "29_8") (pintype "passive"))
    )
    (net (code "91") (name "unconnected-(P1-30-Pad10)") (class "Default")
      (node (ref "P1") (pin "10") (pinfunction "30_10") (pintype "passive"))
    )
    (net (code "92") (name "unconnected-(P1-32-Pad14)") (class "Default")
      (node (ref "P1") (pin "14") (pinfunction "32_14") (pintype "passive"))
    )
    (net (code "93") (name "unconnected-(P1-33-Pad16)") (class "Default")
      (node (ref "P1") (pin "16") (pinfunction "33_16") (pintype "passive"))
    )
    (net (code "94") (name "unconnected-(P1-34-Pad18)") (class "Default")
      (node (ref "P1") (pin "18") (pinfunction "34_18") (pintype "passive"))
    )
    (net (code "95") (name "unconnected-(P1-36-Pad22)") (class "Default")
      (node (ref "P1") (pin "22") (pinfunction "36_22") (pintype "passive"))
    )
    (net (code "96") (name "unconnected-(P1-37-Pad24)") (class "Default")
      (node (ref "P1") (pin "24") (pinfunction "37_24") (pintype "passive"))
    )
    (net (code "97") (name "unconnected-(P1-38-Pad26)") (class "Default")
      (node (ref "P1") (pin "26") (pinfunction "38_26") (pintype "passive"))
    )
    (net (code "98") (name "unconnected-(P1-39-Pad28)") (class "Default")
      (node (ref "P1") (pin "28") (pinfunction "39_28") (pintype "passive"))
    )
    (net (code "99") (name "unconnected-(P1-40-Pad30)") (class "Default")
      (node (ref "P1") (pin "30") (pinfunction "40_30") (pintype "passive"))
    )
    (net (code "100") (name "unconnected-(P1-41-Pad32)") (class "Default")
      (node (ref "P1") (pin "32") (pinfunction "41_32") (pintype "passive"))
    )
    (net (code "101") (name "unconnected-(P1-42-Pad34)") (class "Default")
      (node (ref "P1") (pin "34") (pinfunction "42_34") (pintype "passive"))
    )
    (net (code "102") (name "unconnected-(P1-43-Pad36)") (class "Default")
      (node (ref "P1") (pin "36") (pinfunction "43_36") (pintype "passive"))
    )
    (net (code "103") (name "unconnected-(P1-44-Pad38)") (class "Default")
      (node (ref "P1") (pin "38") (pinfunction "44_38") (pintype "passive"))
    )
    (net (code "104") (name "unconnected-(P2-Pad5)") (class "Default")
      (node (ref "P2") (pin "5") (pinfunction "5_5") (pintype "passive"))
    )
    (net (code "105") (name "unconnected-(P2-Pad6)") (class "Default")
      (node (ref "P2") (pin "6") (pinfunction "6_6") (pintype "passive"))
    )
    (net (code "106") (name "unconnected-(P2-Pad7)") (class "Default")
      (node (ref "P2") (pin "7") (pinfunction "7_7") (pintype "passive"))
    )
    (net (code "107") (name "unconnected-(P2-Pad8)") (class "Default")
      (node (ref "P2") (pin "8") (pinfunction "8_8") (pintype "passive"))
    )
    (net (code "108") (name "unconnected-(P2-Pad9)") (class "Default")
      (node (ref "P2") (pin "9") (pinfunction "9_9") (pintype "passive"))
    )
    (net (code "109") (name "unconnected-(P2-Pad10)") (class "Default")
      (node (ref "P2") (pin "10") (pinfunction "10_10") (pintype "passive"))
    )
    (net (code "110") (name "unconnected-(P2-Pad11)") (class "Default")
      (node (ref "P2") (pin "11") (pinfunction "11_11") (pintype "passive"))
    )
    (net (code "111") (name "unconnected-(P2-Pad12)") (class "Default")
      (node (ref "P2") (pin "12") (pinfunction "12_12") (pintype "passive"))
    )
    (net (code "112") (name "unconnected-(P2-Pad13)") (class "Default")
      (node (ref "P2") (pin "13") (pinfunction "13_13") (pintype "passive"))
    )
    (net (code "113") (name "unconnected-(P2-Pad14)") (class "Default")
      (node (ref "P2") (pin "14") (pinfunction "14_14") (pintype "passive"))
    )
    (net (code "114") (name "unconnected-(P2-Pad15)") (class "Default")
      (node (ref "P2") (pin "15") (pinfunction "15_15") (pintype "passive"))
    )
    (net (code "115") (name "unconnected-(P2-Pad16)") (class "Default")
      (node (ref "P2") (pin "16") (pinfunction "16_16") (pintype "passive"))
    )
    (net (code "116") (name "unconnected-(P2-Pad17)") (class "Default")
      (node (ref "P2") (pin "17") (pinfunction "17_17") (pintype "passive"))
    )
    (net (code "117") (name "unconnected-(P2-Pad18)") (class "Default")
      (node (ref "P2") (pin "18") (pinfunction "18_18") (pintype "passive"))
    )
    (net (code "118") (name "unconnected-(P2-Pad21)") (class "Default")
      (node (ref "P2") (pin "21") (pinfunction "21_21") (pintype "passive"))
    )
    (net (code "119") (name "unconnected-(P2-Pad22)") (class "Default")
      (node (ref "P2") (pin "22") (pinfunction "22_22") (pintype "passive"))
    )
    (net (code "120") (name "unconnected-(P2-Pad23)") (class "Default")
      (node (ref "P2") (pin "23") (pinfunction "23_23") (pintype "passive"))
    )
    (net (code "121") (name "unconnected-(P2-Pad24)") (class "Default")
      (node (ref "P2") (pin "24") (pinfunction "24_24") (pintype "passive"))
    )
    (net (code "122") (name "unconnected-(P2-Pad25)") (class "Default")
      (node (ref "P2") (pin "25") (pinfunction "25_25") (pintype "passive"))
    )
    (net (code "123") (name "unconnected-(P2-Pad26)") (class "Default")
      (node (ref "P2") (pin "26") (pinfunction "26_26") (pintype "passive"))
    )
    (net (code "124") (name "unconnected-(P2-Pad27)") (class "Default")
      (node (ref "P2") (pin "27") (pinfunction "27_27") (pintype "passive"))
    )
    (net (code "125") (name "unconnected-(P2-Pad31)") (class "Default")
      (node (ref "P2") (pin "31") (pinfunction "31_31") (pintype "passive"))
    )
    (net (code "126") (name "unconnected-(P2-Pad32)") (class "Default")
      (node (ref "P2") (pin "32") (pinfunction "32_32") (pintype "passive"))
    )
    (net (code "127") (name "unconnected-(U2-DLCKM-Pad54)") (class "Default")
      (node (ref "U2") (pin "54") (pinfunction "DLCKM_54") (pintype "output"))
    )
    (net (code "128") (name "unconnected-(U2-DLOMA-Pad17)") (class "Default")
      (node (ref "U2") (pin "17") (pinfunction "DLOMA_17") (pintype "output"))
    )
    (net (code "129") (name "unconnected-(U2-DLOMB-Pad28)") (class "Default")
      (node (ref "U2") (pin "28") (pinfunction "DLOMB_28") (pintype "output"))
    )
    (net (code "130") (name "unconnected-(U2-DLOMH-Pad77)") (class "Default")
      (node (ref "U2") (pin "77") (pinfunction "DLOMH_77") (pintype "output"))
    )
    (net (code "131") (name "unconnected-(U2-DLOPA-Pad18)") (class "Default")
      (node (ref "U2") (pin "18") (pinfunction "DLOPA_18") (pintype "output"))
    )
    (net (code "132") (name "unconnected-(U2-DLOPB-Pad29)") (class "Default")
      (node (ref "U2") (pin "29") (pinfunction "DLOPB_29") (pintype "output"))
    )
    (net (code "133") (name "unconnected-(U2-DLOPH-Pad78)") (class "Default")
      (node (ref "U2") (pin "78") (pinfunction "DLOPH_78") (pintype "output"))
    )
    (net (code "134") (name "unconnected-(U2-DMCKN-Pad111)") (class "Default")
      (node (ref "U2") (pin "111") (pinfunction "DMCKN_111") (pintype "output"))
    )
    (net (code "135") (name "unconnected-(U2-DMCKP-Pad103)") (class "Default")
      (node (ref "U2") (pin "103") (pinfunction "DMCKP_103") (pintype "output"))
    )
    (net (code "136") (name "unconnected-(U2-DMO1N-Pad110)") (class "Default")
      (node (ref "U2") (pin "110") (pinfunction "DMO1N_110") (pintype "output"))
    )
    (net (code "137") (name "unconnected-(U2-DMO1P-Pad102)") (class "Default")
      (node (ref "U2") (pin "102") (pinfunction "DMO1P_102") (pintype "output"))
    )
    (net (code "138") (name "unconnected-(U2-DMO2N-Pad112)") (class "Default")
      (node (ref "U2") (pin "112") (pinfunction "DMO2N_112") (pintype "output"))
    )
    (net (code "139") (name "unconnected-(U2-DMO2P-Pad104)") (class "Default")
      (node (ref "U2") (pin "104") (pinfunction "DMO2P_104") (pintype "output"))
    )
    (net (code "140") (name "unconnected-(U2-DMO3N-Pad109)") (class "Default")
      (node (ref "U2") (pin "109") (pinfunction "DMO3N_109") (pintype "output"))
    )
    (net (code "141") (name "unconnected-(U2-DMO3P-Pad101)") (class "Default")
      (node (ref "U2") (pin "101") (pinfunction "DMO3P_101") (pintype "output"))
    )
    (net (code "142") (name "unconnected-(U2-DMO4N-Pad113)") (class "Default")
      (node (ref "U2") (pin "113") (pinfunction "DMO4N_113") (pintype "output"))
    )
    (net (code "143") (name "unconnected-(U2-DMO4P-Pad105)") (class "Default")
      (node (ref "U2") (pin "105") (pinfunction "DMO4P_105") (pintype "output"))
    )
    (net (code "144") (name "unconnected-(U2-NC-Pad1)") (class "Default")
      (node (ref "U2") (pin "1") (pinfunction "NC_1") (pintype "passive"))
    )
    (net (code "145") (name "unconnected-(U2-NC-Pad9)") (class "Default")
      (node (ref "U2") (pin "9") (pinfunction "NC_9") (pintype "passive"))
    )
    (net (code "146") (name "unconnected-(U2-NC-Pad20)") (class "Default")
      (node (ref "U2") (pin "20") (pinfunction "NC_20") (pintype "passive"))
    )
    (net (code "147") (name "unconnected-(U2-NC-Pad21)") (class "Default")
      (node (ref "U2") (pin "21") (pinfunction "NC_21") (pintype "passive"))
    )
    (net (code "148") (name "unconnected-(U2-NC-Pad22)") (class "Default")
      (node (ref "U2") (pin "22") (pinfunction "NC_22") (pintype "passive"))
    )
    (net (code "149") (name "unconnected-(U2-NC-Pad23)") (class "Default")
      (node (ref "U2") (pin "23") (pinfunction "NC_23") (pintype "passive"))
    )
    (net (code "150") (name "unconnected-(U2-NC-Pad24)") (class "Default")
      (node (ref "U2") (pin "24") (pinfunction "NC_24") (pintype "passive"))
    )
    (net (code "151") (name "unconnected-(U2-NC-Pad25)") (class "Default")
      (node (ref "U2") (pin "25") (pinfunction "NC_25") (pintype "passive"))
    )
    (net (code "152") (name "unconnected-(U2-NC-Pad32)") (class "Default")
      (node (ref "U2") (pin "32") (pinfunction "NC_32") (pintype "passive"))
    )
    (net (code "153") (name "unconnected-(U2-NC-Pad33)") (class "Default")
      (node (ref "U2") (pin "33") (pinfunction "NC_33") (pintype "passive"))
    )
    (net (code "154") (name "unconnected-(U2-NC-Pad34)") (class "Default")
      (node (ref "U2") (pin "34") (pinfunction "NC_34") (pintype "passive"))
    )
    (net (code "155") (name "unconnected-(U2-NC-Pad36)") (class "Default")
      (node (ref "U2") (pin "36") (pinfunction "NC_36") (pintype "passive"))
    )
    (net (code "156") (name "unconnected-(U2-NC-Pad43)") (class "Default")
      (node (ref "U2") (pin "43") (pinfunction "NC_43") (pintype "passive"))
    )
    (net (code "157") (name "unconnected-(U2-NC-Pad44)") (class "Default")
      (node (ref "U2") (pin "44") (pinfunction "NC_44") (pintype "passive"))
    )
    (net (code "158") (name "unconnected-(U2-NC-Pad45)") (class "Default")
      (node (ref "U2") (pin "45") (pinfunction "NC_45") (pintype "passive"))
    )
    (net (code "159") (name "unconnected-(U2-NC-Pad47)") (class "Default")
      (node (ref "U2") (pin "47") (pinfunction "NC_47") (pintype "passive"))
    )
    (net (code "160") (name "unconnected-(U2-NC-Pad69)") (class "Default")
      (node (ref "U2") (pin "69") (pinfunction "NC_69") (pintype "passive"))
    )
    (net (code "161") (name "unconnected-(U2-NC-Pad74)") (class "Default")
      (node (ref "U2") (pin "74") (pinfunction "NC_74") (pintype "passive"))
    )
    (net (code "162") (name "unconnected-(U2-NC-Pad80)") (class "Default")
      (node (ref "U2") (pin "80") (pinfunction "NC_80") (pintype "passive"))
    )
    (net (code "163") (name "unconnected-(U2-NC-Pad85)") (class "Default")
      (node (ref "U2") (pin "85") (pinfunction "NC_85") (pintype "passive"))
    )
    (net (code "164") (name "unconnected-(U2-NC-Pad91)") (class "Default")
      (node (ref "U2") (pin "91") (pinfunction "NC_91") (pintype "passive"))
    )
    (net (code "165") (name "unconnected-(U2-NC-Pad100)") (class "Default")
      (node (ref "U2") (pin "100") (pinfunction "NC_100") (pintype "passive"))
    )
    (net (code "166") (name "unconnected-(U2-NC-Pad106)") (class "Default")
      (node (ref "U2") (pin "106") (pinfunction "NC_106") (pintype "passive"))
    )
    (net (code "167") (name "unconnected-(U2-NC-Pad108)") (class "Default")
      (node (ref "U2") (pin "108") (pinfunction "NC_108") (pintype "passive"))
    )
    (net (code "168") (name "unconnected-(U2-Pad114)") (class "Default")
      (node (ref "U2") (pin "114") (pinfunction "114_114") (pintype "passive"))
    )
    (net (code "169") (name "unconnected-(U2-SDO-Pad52)") (class "Default")
      (node (ref "U2") (pin "52") (pinfunction "SDO_52") (pintype "output"))
    )
    (net (code "170") (name "unconnected-(U2-TAMON-Pad26)") (class "Default")
      (node (ref "U2") (pin "26") (pinfunction "TAMON_26") (pintype "output"))
    )
    (net (code "171") (name "unconnected-(U2-TENABLE-Pad49)") (class "Default")
      (node (ref "U2") (pin "49") (pinfunction "TENABLE_49") (pintype "input"))
    )
    (net (code "172") (name "unconnected-(U2-TOUT-Pad65)") (class "Default")
      (node (ref "U2") (pin "65") (pinfunction "TOUT_65") (pintype "output"))
    )
    (net (code "173") (name "unconnected-(U2-XTRIG-Pad76)") (class "Default")
      (node (ref "U2") (pin "76") (pinfunction "XTRIG_76") (pintype "input"))
    )
    (net (code "174") (name "unconnected-(U4-BYPASS-Pad4)") (class "Default")
      (node (ref "U4") (pin "4") (pinfunction "BYPASS_4") (pintype "bidirectional"))
    )
    (net (code "175") (name "unconnected-(U6-1A1-Pad47)") (class "Default")
      (node (ref "U6") (pin "47") (pinfunction "1A1_47") (pintype "bidirectional"))
    )
    (net (code "176") (name "unconnected-(U6-1A2-Pad46)") (class "Default")
      (node (ref "U6") (pin "46") (pinfunction "1A2_46") (pintype "bidirectional"))
    )
    (net (code "177") (name "unconnected-(U6-1A3-Pad44)") (class "Default")
      (node (ref "U6") (pin "44") (pinfunction "1A3_44") (pintype "bidirectional"))
    )
    (net (code "178") (name "unconnected-(U6-1A4-Pad43)") (class "Default")
      (node (ref "U6") (pin "43") (pinfunction "1A4_43") (pintype "bidirectional"))
    )
    (net (code "179") (name "unconnected-(U6-1A5-Pad41)") (class "Default")
      (node (ref "U6") (pin "41") (pinfunction "1A5_41") (pintype "bidirectional"))
    )
    (net (code "180") (name "unconnected-(U6-1A6-Pad40)") (class "Default")
      (node (ref "U6") (pin "40") (pinfunction "1A6_40") (pintype "bidirectional"))
    )
    (net (code "181") (name "unconnected-(U6-1B1-Pad2)") (class "Default")
      (node (ref "U6") (pin "2") (pinfunction "1B1_2") (pintype "bidirectional"))
    )
    (net (code "182") (name "unconnected-(U6-1B2-Pad3)") (class "Default")
      (node (ref "U6") (pin "3") (pinfunction "1B2_3") (pintype "bidirectional"))
    )
    (net (code "183") (name "unconnected-(U6-1B3-Pad5)") (class "Default")
      (node (ref "U6") (pin "5") (pinfunction "1B3_5") (pintype "bidirectional"))
    )
    (net (code "184") (name "unconnected-(U6-1B4-Pad6)") (class "Default")
      (node (ref "U6") (pin "6") (pinfunction "1B4_6") (pintype "bidirectional"))
    )
    (net (code "185") (name "unconnected-(U6-1B5-Pad8)") (class "Default")
      (node (ref "U6") (pin "8") (pinfunction "1B5_8") (pintype "bidirectional"))
    )
    (net (code "186") (name "unconnected-(U6-1B6-Pad9)") (class "Default")
      (node (ref "U6") (pin "9") (pinfunction "1B6_9") (pintype "bidirectional"))
    )
    (net (code "187") (name "unconnected-(U7-BYPASS-Pad4)") (class "Default")
      (node (ref "U7") (pin "4") (pinfunction "BYPASS_4") (pintype "bidirectional"))
    )
    (net (code "188") (name "unconnected-(U9-NC-Pad6)") (class "Default")
      (node (ref "U9") (pin "6") (pinfunction "NC_6") (pintype "passive"))
    )
    (net (code "189") (name "unconnected-(U9-NC-Pad9)") (class "Default")
      (node (ref "U9") (pin "9") (pinfunction "NC_9") (pintype "passive"))
    )
  )
)
